# wemos-d1-screw-terminal-v1_0.net
KiCad netlist of a schematic drawn in EAGLE
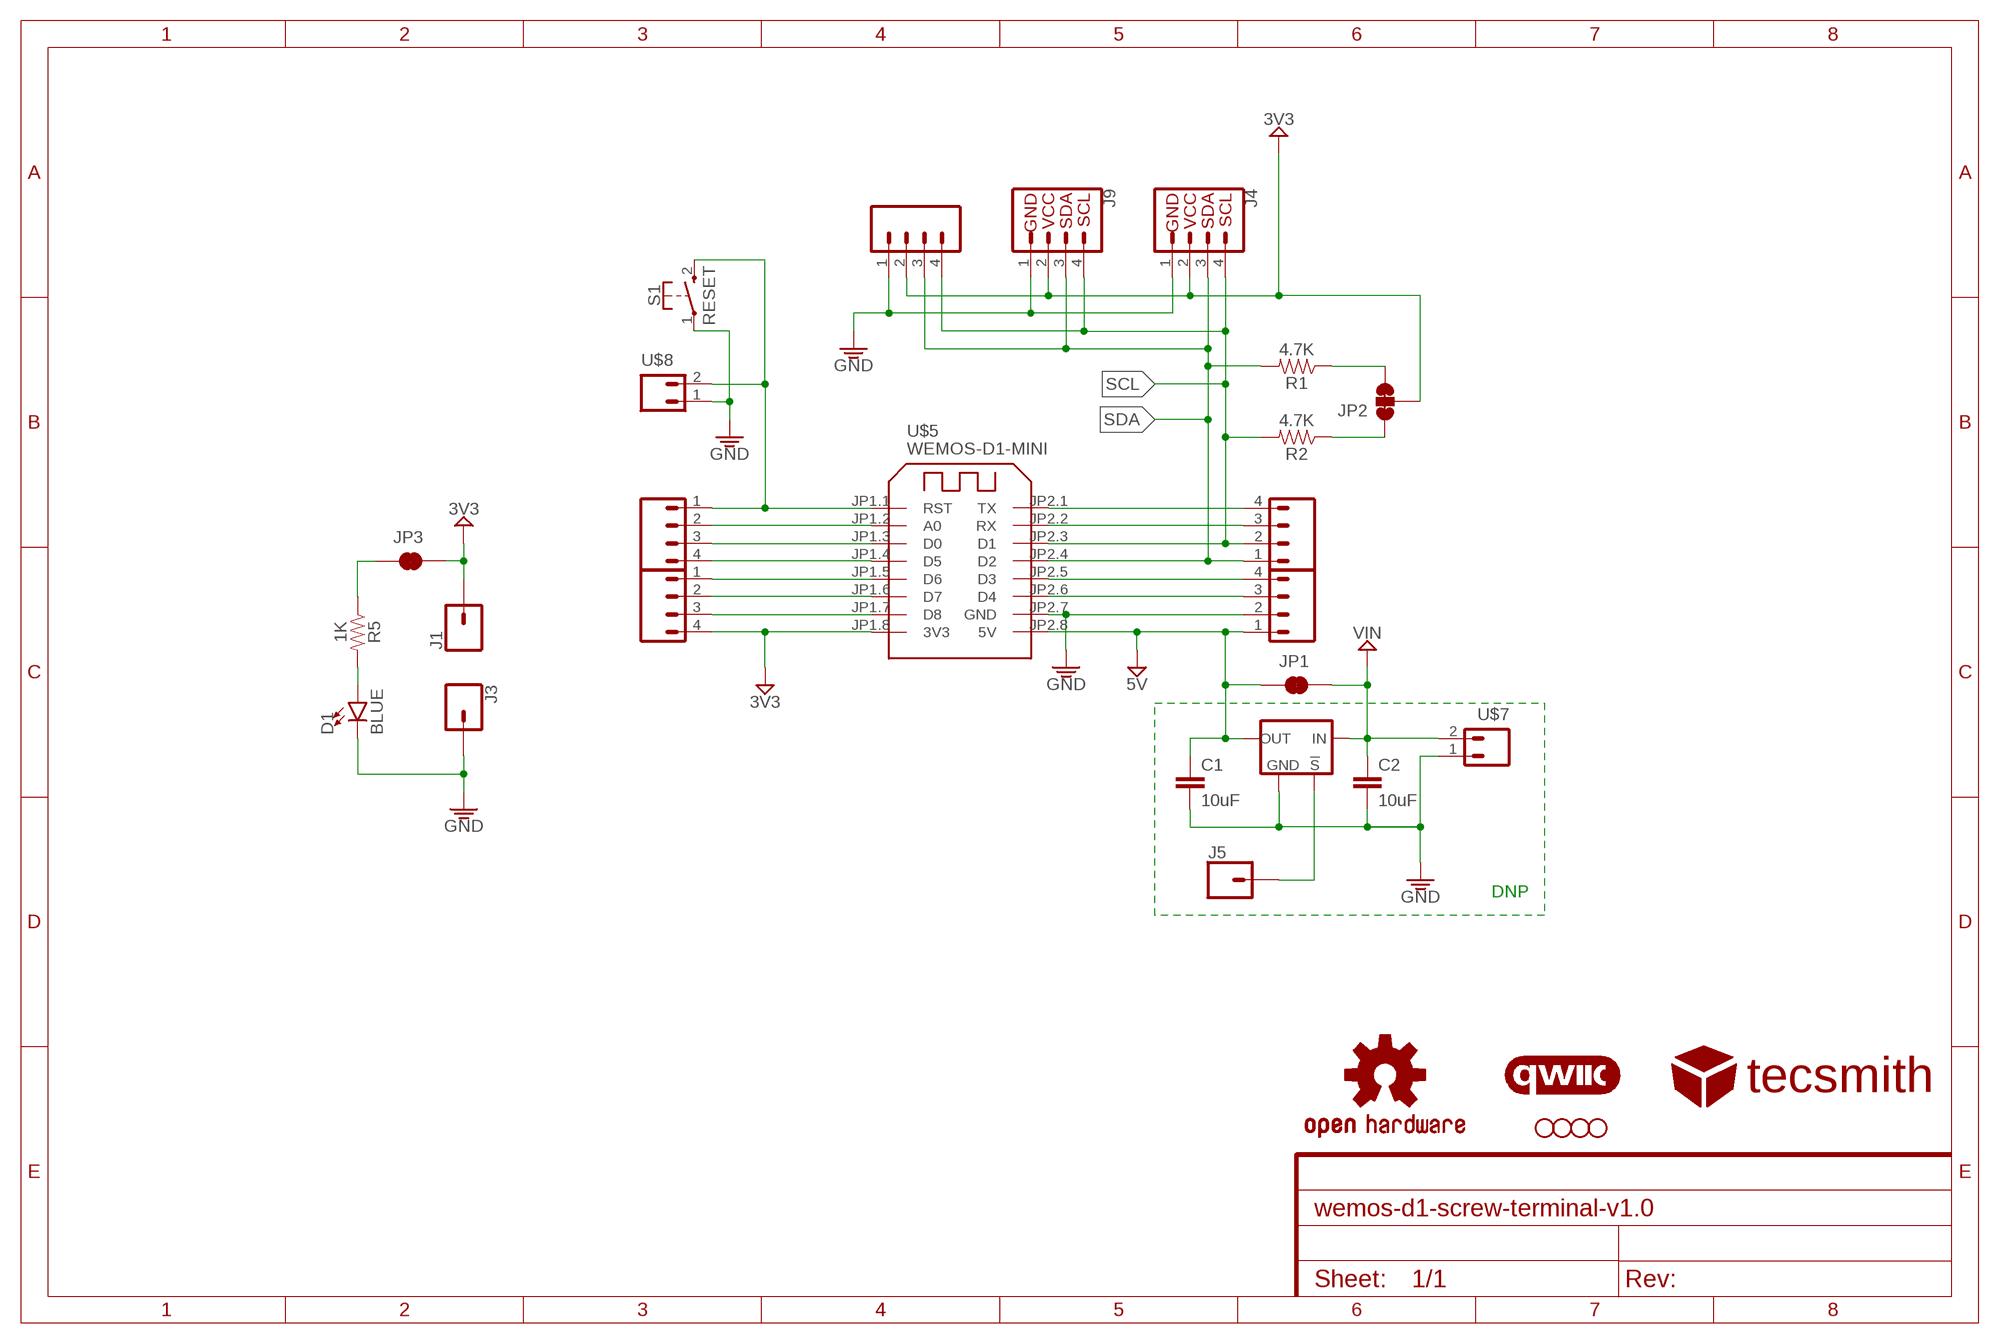
[diagram p0: schematic, sheet 1]

(export (version "E")
  (design (tool "Eeschema 10.0.6"))
  (components
    (comp (ref "C1")
      (value "10uF")
      (footprint "eagle-import:0805")
      (libsource (lib "eagle-import") (part "10UF-0805-10V-10%"))
    )
    (comp (ref "C2")
      (value "10uF")
      (footprint "eagle-import:0805")
      (libsource (lib "eagle-import") (part "10UF-0805-10V-10%"))
    )
    (comp (ref "D1")
      (value "BLUE")
      (footprint "eagle-import:LED-0603")
      (libsource (lib "eagle-import") (part "LED-BLUE0603"))
    )
    (comp (ref "H1")
      (value "STAND-OFF")
      (footprint "eagle-import:STAND-OFF")
      (libsource (lib "eagle-import") (part "STAND-OFF"))
    )
    (comp (ref "H2")
      (value "STAND-OFF")
      (footprint "eagle-import:STAND-OFF")
      (libsource (lib "eagle-import") (part "STAND-OFF"))
    )
    (comp (ref "H5")
      (value "STAND-OFF")
      (footprint "eagle-import:STAND-OFF")
      (libsource (lib "eagle-import") (part "STAND-OFF"))
    )
    (comp (ref "H6")
      (value "STAND-OFF")
      (footprint "eagle-import:STAND-OFF")
      (libsource (lib "eagle-import") (part "STAND-OFF"))
    )
    (comp (ref "J1")
      (value "CONN_01PTH_NO_SILK_YES_STOP")
      (footprint "eagle-import:1X01_NO_SILK")
      (libsource (lib "eagle-import") (part "CONN_01PTH_NO_SILK_YES_STOP"))
    )
    (comp (ref "J2")
      (value "CONN_04PTH")
      (footprint "eagle-import:1X04")
      (libsource (lib "eagle-import") (part "CONN_04PTH"))
    )
    (comp (ref "J3")
      (value "CONN_01PTH_NO_SILK_YES_STOP")
      (footprint "eagle-import:1X01_NO_SILK")
      (libsource (lib "eagle-import") (part "CONN_01PTH_NO_SILK_YES_STOP"))
    )
    (comp (ref "J4")
      (value "QWIIC_RIGHT_ANGLE")
      (footprint "eagle-import:JST04_1MM_RA")
      (libsource (lib "eagle-import") (part "QWIIC_CONNECTORJS-1MM"))
    )
    (comp (ref "J5")
      (value "CONN_01PTH_NO_SILK_YES_STOP")
      (footprint "eagle-import:1X01_NO_SILK")
      (libsource (lib "eagle-import") (part "CONN_01PTH_NO_SILK_YES_STOP"))
    )
    (comp (ref "J9")
      (value "QWIIC_RIGHT_ANGLE")
      (footprint "eagle-import:JST04_1MM_RA")
      (libsource (lib "eagle-import") (part "QWIIC_CONNECTORJS-1MM"))
    )
    (comp (ref "JP1")
      (value "JUMPER-COMBO_2_NC_TRACE")
      (footprint "eagle-import:COMBO-JUMPER_2_NC_TRACE")
      (libsource (lib "eagle-import") (part "JUMPER-COMBO_2_NC_TRACE"))
    )
    (comp (ref "JP2")
      (value "JUMPER-SMT_3_2-NC_TRACE_SILK")
      (footprint "eagle-import:SMT-JUMPER_3_2-NC_TRACE_SILK")
      (libsource (lib "eagle-import") (part "JUMPER-SMT_3_2-NC_TRACE_SILK"))
    )
    (comp (ref "JP3")
      (value "JUMPER-SMT_2_NC_TRACE_SILK")
      (footprint "eagle-import:SMT-JUMPER_2_NC_TRACE_SILK")
      (libsource (lib "eagle-import") (part "JUMPER-SMT_2_NC_TRACE_SILK"))
    )
    (comp (ref "LOGO1")
      (value "OSHW-LOGOS")
      (footprint "eagle-import:OSHW-LOGO-S")
      (libsource (lib "eagle-import") (part "OSHW-LOGOS"))
    )
    (comp (ref "LOGO2")
      (value "QWIIC_LOGO_6MM")
      (footprint "eagle-import:QWIIC_6MM")
      (libsource (lib "eagle-import") (part "QWIIC_LOGO_6MM"))
    )
    (comp (ref "R1")
      (value "4.7K")
      (footprint "eagle-import:0805")
      (libsource (lib "eagle-import") (part "RESISTOR0805"))
    )
    (comp (ref "R2")
      (value "4.7K")
      (footprint "eagle-import:0805")
      (libsource (lib "eagle-import") (part "RESISTOR0805"))
    )
    (comp (ref "R5")
      (value "1K")
      (footprint "eagle-import:0603")
      (libsource (lib "eagle-import") (part "330OHM-0603-1/10W-1%"))
    )
    (comp (ref "S1")
      (value "RESET")
      (footprint "eagle-import:SKRKAEE020")
      (libsource (lib "eagle-import") (part "MOMENTARY-SWITCH-SPST-1"))
    )
    (comp (ref "U$1")
      (value "CON_04SCREW")
      (footprint "eagle-import:WURTH_2431_3.5MM_4X_SCREW")
      (libsource (lib "eagle-import") (part "CON_04SCREW"))
    )
    (comp (ref "U$2")
      (value "CON_04SCREW")
      (footprint "eagle-import:WURTH_2431_3.5MM_4X_SCREW")
      (libsource (lib "eagle-import") (part "CON_04SCREW"))
    )
    (comp (ref "U$3")
      (value "CON_04SCREW")
      (footprint "eagle-import:WURTH_2431_3.5MM_4X_SCREW")
      (libsource (lib "eagle-import") (part "CON_04SCREW"))
    )
    (comp (ref "U$4")
      (value "CON_04SCREW")
      (footprint "eagle-import:WURTH_2431_3.5MM_4X_SCREW")
      (libsource (lib "eagle-import") (part "CON_04SCREW"))
    )
    (comp (ref "U$5")
      (value "WEMOS-D1-MINI")
      (footprint "eagle-import:WEMOS-D1-MINI")
      (libsource (lib "eagle-import") (part "WEMOS-D1-MINI"))
    )
    (comp (ref "U$6")
      (value "POLOLU-VREG")
      (footprint "eagle-import:TO-220+1")
      (libsource (lib "eagle-import") (part "POLOLU-VREG"))
    )
    (comp (ref "U$7")
      (value "CON_02SCREW")
      (footprint "eagle-import:WURTH_2431_3.5MM_2X_SCREW")
      (libsource (lib "eagle-import") (part "CON_02SCREW"))
    )
    (comp (ref "U$8")
      (value "JST-PH-2")
      (footprint "eagle-import:JST-PH2")
      (libsource (lib "eagle-import") (part "JST-PH-2"))
    )
    (comp (ref "U$9")
      (value "TECSMITH-LOGO")
      (footprint "eagle-import:TECSMITH-LOGO")
      (libsource (lib "eagle-import") (part "TECSMITH-LOGO"))
    )
  )
  (nets
    (net (code "1") (name "3V3") (class "Default")
      (node (ref "J1") (pin "1") (pinfunction "1_1") (pintype "passive"))
      (node (ref "J2") (pin "2") (pinfunction "2_2") (pintype "passive"))
      (node (ref "J4") (pin "2") (pinfunction "2_2") (pintype "power_in"))
      (node (ref "J9") (pin "2") (pinfunction "2_2") (pintype "power_in"))
      (node (ref "JP2") (pin "2") (pinfunction "2_2") (pintype "passive"))
      (node (ref "JP3") (pin "2") (pinfunction "2_2") (pintype "passive"))
      (node (ref "U$2") (pin "4") (pinfunction "4_4") (pintype "passive"))
      (node (ref "U$5") (pin "JP1.8") (pinfunction "3V3_JP1.8") (pintype "power_in"))
    )
    (net (code "2") (name "5V") (class "Default")
      (node (ref "C1") (pin "1") (pinfunction "1_1") (pintype "passive"))
      (node (ref "JP1") (pin "1") (pinfunction "1_1") (pintype "passive"))
      (node (ref "JP1") (pin "3") (pinfunction "1_3") (pintype "passive"))
      (node (ref "U$3") (pin "1") (pinfunction "1_1") (pintype "passive"))
      (node (ref "U$5") (pin "JP2.8") (pinfunction "5V_JP2.8") (pintype "power_in"))
      (node (ref "U$6") (pin "OUT") (pinfunction "OUT_OUT") (pintype "output"))
    )
    (net (code "3") (name "GND") (class "Default")
      (node (ref "C1") (pin "2") (pinfunction "2_2") (pintype "passive"))
      (node (ref "C2") (pin "2") (pinfunction "2_2") (pintype "passive"))
      (node (ref "D1") (pin "C") (pinfunction "C_C") (pintype "passive"))
      (node (ref "J2") (pin "1") (pinfunction "1_1") (pintype "passive"))
      (node (ref "J3") (pin "1") (pinfunction "1_1") (pintype "passive"))
      (node (ref "J4") (pin "1") (pinfunction "1_1") (pintype "power_in"))
      (node (ref "J9") (pin "1") (pinfunction "1_1") (pintype "power_in"))
      (node (ref "S1") (pin "1") (pinfunction "1_1") (pintype "passive"))
      (node (ref "U$3") (pin "2") (pinfunction "2_2") (pintype "passive"))
      (node (ref "U$5") (pin "JP2.7") (pinfunction "GND_JP2.7") (pintype "power_in"))
      (node (ref "U$6") (pin "GND") (pinfunction "GND_GND") (pintype "power_in"))
      (node (ref "U$7") (pin "1") (pinfunction "1_1") (pintype "passive"))
      (node (ref "U$8") (pin "1") (pinfunction "1_1") (pintype "passive"))
    )
    (net (code "4") (name "Net-(D1-PadA)") (class "Default")
      (node (ref "D1") (pin "A") (pinfunction "A_A") (pintype "passive"))
      (node (ref "R5") (pin "2") (pinfunction "2_2") (pintype "passive"))
    )
    (net (code "5") (name "Net-(JP2-Pad1)") (class "Default")
      (node (ref "JP2") (pin "1") (pinfunction "1_1") (pintype "passive"))
      (node (ref "R2") (pin "1") (pinfunction "1_1") (pintype "passive"))
    )
    (net (code "6") (name "Net-(JP2-Pad3)") (class "Default")
      (node (ref "JP2") (pin "3") (pinfunction "3_3") (pintype "passive"))
      (node (ref "R1") (pin "1") (pinfunction "1_1") (pintype "passive"))
    )
    (net (code "7") (name "Net-(JP3-Pad1)") (class "Default")
      (node (ref "JP3") (pin "1") (pinfunction "1_1") (pintype "passive"))
      (node (ref "R5") (pin "1") (pinfunction "1_1") (pintype "passive"))
    )
    (net (code "8") (name "Net-(S1-3)") (class "Default")
      (node (ref "S1") (pin "2") (pinfunction "3_2") (pintype "passive"))
      (node (ref "U$1") (pin "1") (pinfunction "1_1") (pintype "passive"))
      (node (ref "U$5") (pin "JP1.1") (pinfunction "RST_JP1.1") (pintype "bidirectional"))
      (node (ref "U$8") (pin "2") (pinfunction "2_2") (pintype "passive"))
    )
    (net (code "9") (name "Net-(U$5-A0)") (class "Default")
      (node (ref "U$1") (pin "2") (pinfunction "2_2") (pintype "passive"))
      (node (ref "U$5") (pin "JP1.2") (pinfunction "A0_JP1.2") (pintype "bidirectional"))
    )
    (net (code "10") (name "Net-(U$5-D0)") (class "Default")
      (node (ref "U$1") (pin "3") (pinfunction "3_3") (pintype "passive"))
      (node (ref "U$5") (pin "JP1.3") (pinfunction "D0_JP1.3") (pintype "bidirectional"))
    )
    (net (code "11") (name "Net-(U$5-D3)") (class "Default")
      (node (ref "U$3") (pin "4") (pinfunction "4_4") (pintype "passive"))
      (node (ref "U$5") (pin "JP2.5") (pinfunction "D3_JP2.5") (pintype "bidirectional"))
    )
    (net (code "12") (name "Net-(U$5-D4)") (class "Default")
      (node (ref "U$3") (pin "3") (pinfunction "3_3") (pintype "passive"))
      (node (ref "U$5") (pin "JP2.6") (pinfunction "D4_JP2.6") (pintype "bidirectional"))
    )
    (net (code "13") (name "Net-(U$5-D5)") (class "Default")
      (node (ref "U$1") (pin "4") (pinfunction "4_4") (pintype "passive"))
      (node (ref "U$5") (pin "JP1.4") (pinfunction "D5_JP1.4") (pintype "bidirectional"))
    )
    (net (code "14") (name "Net-(U$5-D6)") (class "Default")
      (node (ref "U$2") (pin "1") (pinfunction "1_1") (pintype "passive"))
      (node (ref "U$5") (pin "JP1.5") (pinfunction "D6_JP1.5") (pintype "bidirectional"))
    )
    (net (code "15") (name "Net-(U$5-D7)") (class "Default")
      (node (ref "U$2") (pin "2") (pinfunction "2_2") (pintype "passive"))
      (node (ref "U$5") (pin "JP1.6") (pinfunction "D7_JP1.6") (pintype "bidirectional"))
    )
    (net (code "16") (name "Net-(U$5-D8)") (class "Default")
      (node (ref "U$2") (pin "3") (pinfunction "3_3") (pintype "passive"))
      (node (ref "U$5") (pin "JP1.7") (pinfunction "D8_JP1.7") (pintype "bidirectional"))
    )
    (net (code "17") (name "Net-(U$5-RX)") (class "Default")
      (node (ref "U$4") (pin "3") (pinfunction "3_3") (pintype "passive"))
      (node (ref "U$5") (pin "JP2.2") (pinfunction "RX_JP2.2") (pintype "bidirectional"))
    )
    (net (code "18") (name "Net-(U$5-TX)") (class "Default")
      (node (ref "U$4") (pin "4") (pinfunction "4_4") (pintype "passive"))
      (node (ref "U$5") (pin "JP2.1") (pinfunction "TX_JP2.1") (pintype "bidirectional"))
    )
    (net (code "19") (name "Net-(U$6-~{SHDN})") (class "Default")
      (node (ref "J5") (pin "1") (pinfunction "1_1") (pintype "passive"))
      (node (ref "U$6") (pin "!SHDN") (pinfunction "~{SHDN}_!SHDN") (pintype "bidirectional"))
    )
    (net (code "20") (name "SCL") (class "Default")
      (node (ref "J2") (pin "4") (pinfunction "4_4") (pintype "passive"))
      (node (ref "J4") (pin "4") (pinfunction "4_4") (pintype "passive"))
      (node (ref "J9") (pin "4") (pinfunction "4_4") (pintype "passive"))
      (node (ref "R2") (pin "2") (pinfunction "2_2") (pintype "passive"))
      (node (ref "U$4") (pin "2") (pinfunction "2_2") (pintype "passive"))
      (node (ref "U$5") (pin "JP2.3") (pinfunction "D1_JP2.3") (pintype "bidirectional"))
    )
    (net (code "21") (name "SDA") (class "Default")
      (node (ref "J2") (pin "3") (pinfunction "3_3") (pintype "passive"))
      (node (ref "J4") (pin "3") (pinfunction "3_3") (pintype "passive"))
      (node (ref "J9") (pin "3") (pinfunction "3_3") (pintype "passive"))
      (node (ref "R1") (pin "2") (pinfunction "2_2") (pintype "passive"))
      (node (ref "U$4") (pin "1") (pinfunction "1_1") (pintype "passive"))
      (node (ref "U$5") (pin "JP2.4") (pinfunction "D2_JP2.4") (pintype "bidirectional"))
    )
    (net (code "22") (name "VIN") (class "Default")
      (node (ref "C2") (pin "1") (pinfunction "1_1") (pintype "passive"))
      (node (ref "JP1") (pin "2") (pinfunction "2_2") (pintype "passive"))
      (node (ref "JP1") (pin "4") (pinfunction "2_4") (pintype "passive"))
      (node (ref "U$6") (pin "IN") (pinfunction "IN_IN") (pintype "input"))
      (node (ref "U$7") (pin "2") (pinfunction "2_2") (pintype "passive"))
    )
  )
)
